# working.net
KiCad netlist of a schematic drawn in EAGLE
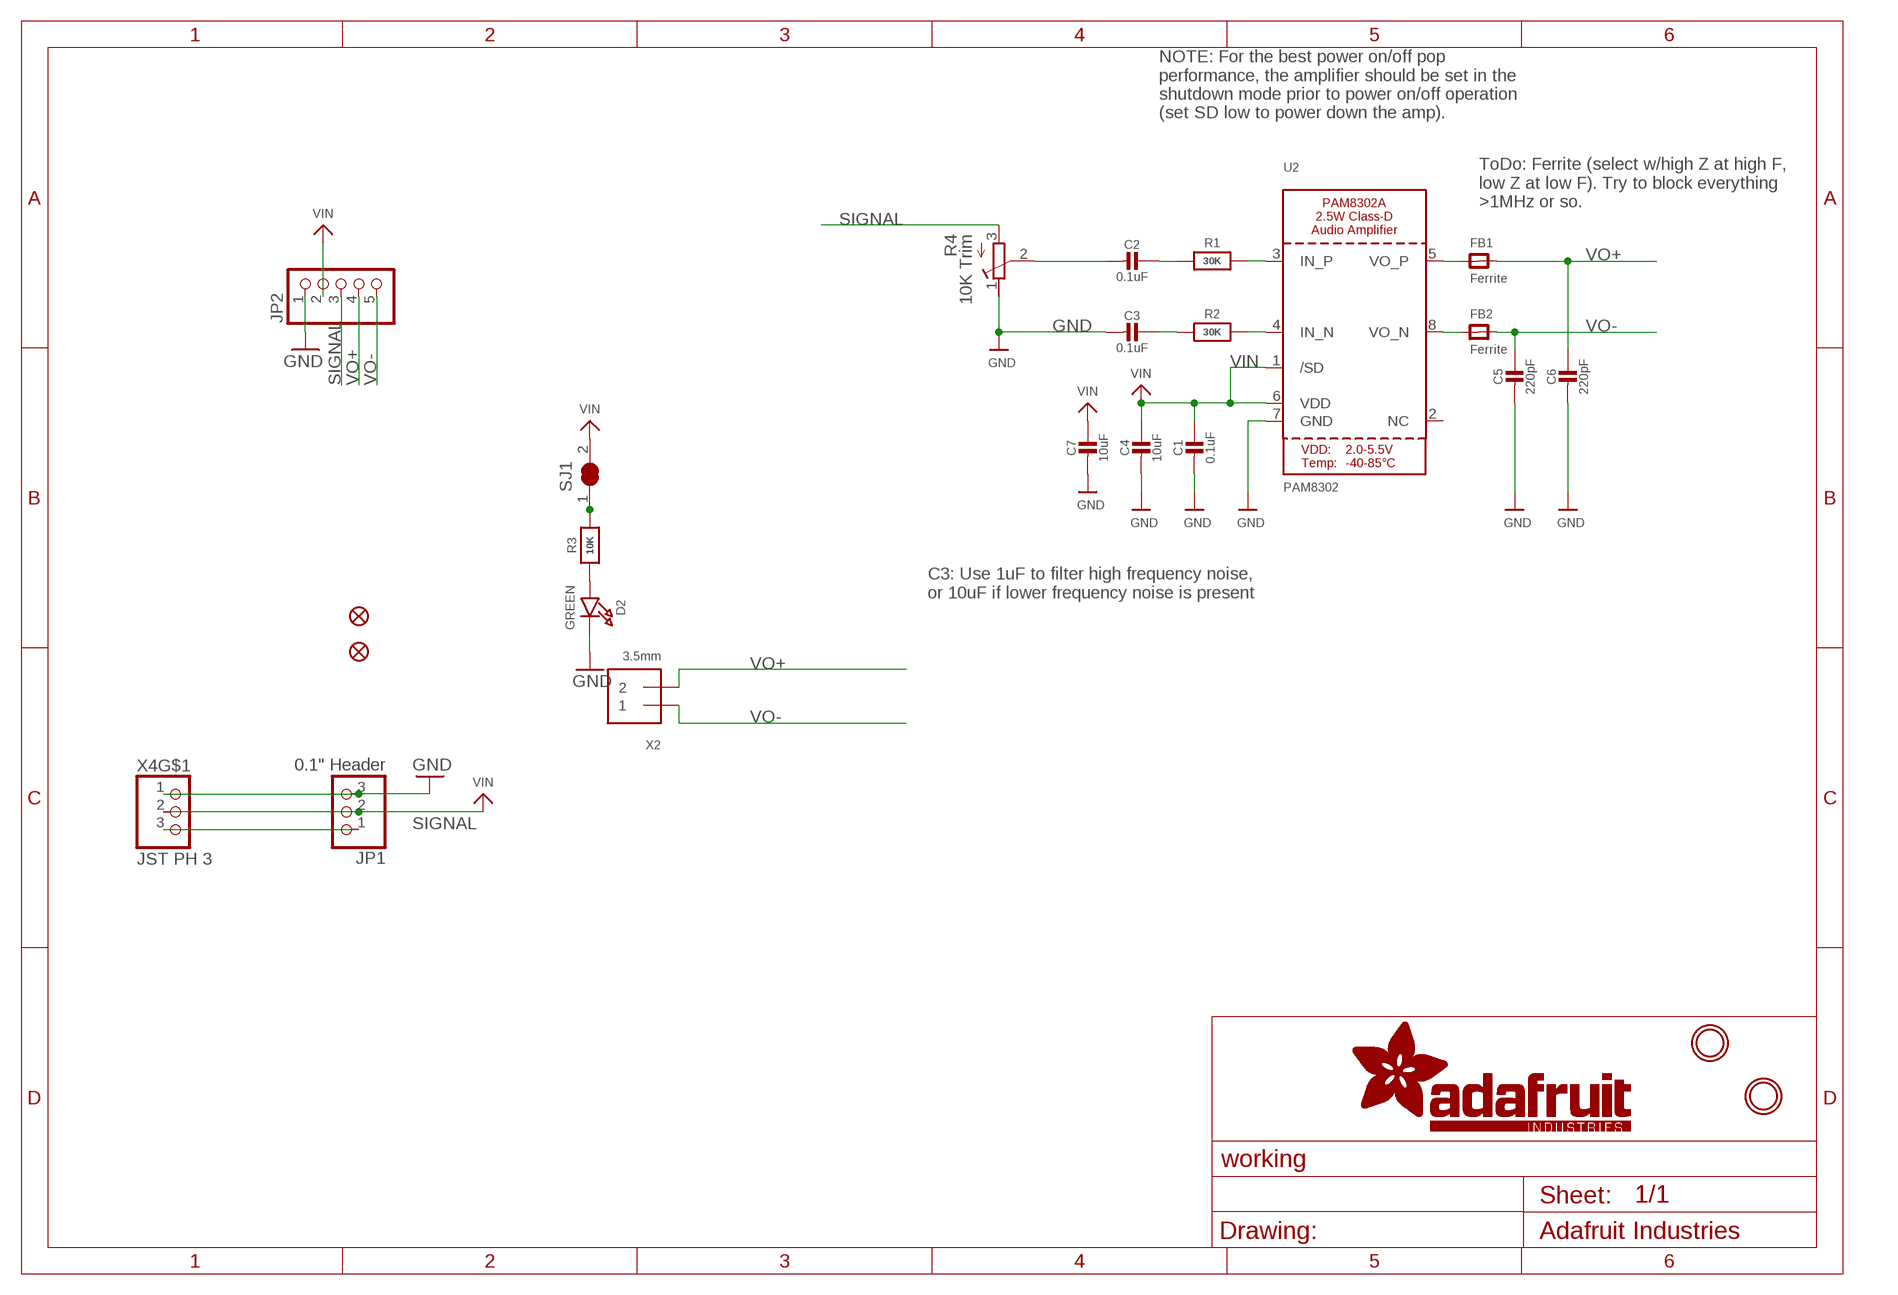
[diagram p0: schematic, sheet 1]

(export (version "E")
  (design (tool "Eeschema 10.0.6"))
  (components
    (comp (ref "C1")
      (value "0.1uF")
      (footprint "eagle-import:0603-NO")
      (libsource (lib "eagle-import") (part "CAP_CERAMIC0603_NO"))
    )
    (comp (ref "C2")
      (value "0.1uF")
      (footprint "eagle-import:0603-NO")
      (libsource (lib "eagle-import") (part "CAP_CERAMIC0603_NO"))
    )
    (comp (ref "C3")
      (value "0.1uF")
      (footprint "eagle-import:0603-NO")
      (libsource (lib "eagle-import") (part "CAP_CERAMIC0603_NO"))
    )
    (comp (ref "C4")
      (value "10uF")
      (footprint "eagle-import:0805-NO")
      (libsource (lib "eagle-import") (part "CAP_CERAMIC0805-NOOUTLINE"))
    )
    (comp (ref "C5")
      (value "220pF")
      (footprint "eagle-import:0603-NO")
      (libsource (lib "eagle-import") (part "CAP_CERAMIC0603_NO"))
    )
    (comp (ref "C6")
      (value "220pF")
      (footprint "eagle-import:0603-NO")
      (libsource (lib "eagle-import") (part "CAP_CERAMIC0603_NO"))
    )
    (comp (ref "C7")
      (value "10uF")
      (footprint "eagle-import:0805-NO")
      (libsource (lib "eagle-import") (part "CAP_CERAMIC0805-NOOUTLINE"))
    )
    (comp (ref "D2")
      (value "GREEN")
      (footprint "eagle-import:CHIPLED_0603_NOOUTLINE")
      (libsource (lib "eagle-import") (part "LED0603_NOOUTLINE"))
    )
    (comp (ref "FB1")
      (value "Ferrite")
      (footprint "eagle-import:0603-NO")
      (libsource (lib "eagle-import") (part "FERRITE-0603NO"))
    )
    (comp (ref "FB2")
      (value "Ferrite")
      (footprint "eagle-import:0603-NO")
      (libsource (lib "eagle-import") (part "FERRITE-0603NO"))
    )
    (comp (ref "FID2")
      (value "FIDUCIAL_1MM")
      (footprint "eagle-import:FIDUCIAL_1MM")
      (libsource (lib "eagle-import") (part "FIDUCIAL_1MM"))
    )
    (comp (ref "FID3")
      (value "FIDUCIAL_1MM")
      (footprint "eagle-import:FIDUCIAL_1MM")
      (libsource (lib "eagle-import") (part "FIDUCIAL_1MM"))
    )
    (comp (ref "JP1")
      (value "0.1\" Header")
      (footprint "eagle-import:1X03_OVAL")
      (libsource (lib "eagle-import") (part "HEADER-1X3"))
    )
    (comp (ref "JP2")
      (value "HEADER-1X570MIL")
      (footprint "eagle-import:1X05_ROUND_70")
      (libsource (lib "eagle-import") (part "HEADER-1X570MIL"))
    )
    (comp (ref "R1")
      (value "30K")
      (footprint "eagle-import:0603-NO")
      (libsource (lib "eagle-import") (part "RESISTOR_0603_NOOUT"))
    )
    (comp (ref "R2")
      (value "30K")
      (footprint "eagle-import:0603-NO")
      (libsource (lib "eagle-import") (part "RESISTOR_0603_NOOUT"))
    )
    (comp (ref "R3")
      (value "10K")
      (footprint "eagle-import:0603-NO")
      (libsource (lib "eagle-import") (part "RESISTOR_0603_NOOUT"))
    )
    (comp (ref "R4")
      (value "10K Trim")
      (footprint "eagle-import:RTRIM3314J")
      (libsource (lib "eagle-import") (part "R-TRIMM3314J"))
    )
    (comp (ref "SJ1")
      (value "SOLDERJUMPER_CLOSED")
      (footprint "eagle-import:SOLDERJUMPER_CLOSEDWIRE")
      (libsource (lib "eagle-import") (part "SOLDERJUMPER_CLOSED"))
    )
    (comp (ref "U$1")
      (value "MOUNTINGHOLE2.5")
      (footprint "eagle-import:MOUNTINGHOLE_2.5_PLATED")
      (libsource (lib "eagle-import") (part "MOUNTINGHOLE2.5"))
    )
    (comp (ref "U$8")
      (value "MOUNTINGHOLE2.5")
      (footprint "eagle-import:MOUNTINGHOLE_2.5_PLATED")
      (libsource (lib "eagle-import") (part "MOUNTINGHOLE2.5"))
    )
    (comp (ref "U2")
      (value "PAM8302")
      (footprint "eagle-import:MSOP8_0.65MM")
      (libsource (lib "eagle-import") (part "AUDIOAMP_PAM8302A"))
    )
    (comp (ref "X2")
      (value "3.5mm")
      (footprint "eagle-import:TERMBLOCK_1X2-3.5MM")
      (libsource (lib "eagle-import") (part "TERMBLOCK_1X2_3.5MM"))
    )
    (comp (ref "X4")
      (value "JST PH 3")
      (footprint "eagle-import:JSTPH3")
      (libsource (lib "eagle-import") (part "CON_JST_PH_3PIN"))
    )
  )
  (nets
    (net (code "1") (name "/SIGNAL") (class "Default")
      (node (ref "JP1") (pin "1") (pinfunction "1_1") (pintype "passive"))
      (node (ref "JP2") (pin "3") (pinfunction "3_3") (pintype "passive"))
      (node (ref "R4") (pin "3") (pinfunction "A_3") (pintype "passive"))
      (node (ref "X4") (pin "3") (pinfunction "3_3") (pintype "passive"))
    )
    (net (code "2") (name "/VO+") (class "Default")
      (node (ref "C6") (pin "1") (pinfunction "1_1") (pintype "passive"))
      (node (ref "FB1") (pin "2") (pinfunction "P$2_2") (pintype "passive"))
      (node (ref "JP2") (pin "4") (pinfunction "4_4") (pintype "passive"))
      (node (ref "X2") (pin "2") (pinfunction "2_2") (pintype "passive"))
    )
    (net (code "3") (name "/VO-") (class "Default")
      (node (ref "C5") (pin "1") (pinfunction "1_1") (pintype "passive"))
      (node (ref "FB2") (pin "2") (pinfunction "P$2_2") (pintype "passive"))
      (node (ref "JP2") (pin "5") (pinfunction "5_5") (pintype "passive"))
      (node (ref "X2") (pin "1") (pinfunction "1_1") (pintype "passive"))
    )
    (net (code "4") (name "GND") (class "Default")
      (node (ref "C1") (pin "2") (pinfunction "2_2") (pintype "passive"))
      (node (ref "C3") (pin "2") (pinfunction "2_2") (pintype "passive"))
      (node (ref "C4") (pin "2") (pinfunction "2_2") (pintype "passive"))
      (node (ref "C5") (pin "2") (pinfunction "2_2") (pintype "passive"))
      (node (ref "C6") (pin "2") (pinfunction "2_2") (pintype "passive"))
      (node (ref "C7") (pin "2") (pinfunction "2_2") (pintype "passive"))
      (node (ref "D2") (pin "C") (pinfunction "C_C") (pintype "passive"))
      (node (ref "JP1") (pin "3") (pinfunction "3_3") (pintype "passive"))
      (node (ref "JP2") (pin "1") (pinfunction "1_1") (pintype "passive"))
      (node (ref "R4") (pin "1") (pinfunction "E_1") (pintype "passive"))
      (node (ref "U2") (pin "7") (pinfunction "GND_7") (pintype "power_in"))
      (node (ref "X4") (pin "1") (pinfunction "1_1") (pintype "passive"))
    )
    (net (code "5") (name "Net-(C2-Pad1)") (class "Default")
      (node (ref "C2") (pin "1") (pinfunction "1_1") (pintype "passive"))
      (node (ref "R1") (pin "1") (pinfunction "1_1") (pintype "passive"))
    )
    (net (code "6") (name "Net-(C3-Pad1)") (class "Default")
      (node (ref "C3") (pin "1") (pinfunction "1_1") (pintype "passive"))
      (node (ref "R2") (pin "1") (pinfunction "1_1") (pintype "passive"))
    )
    (net (code "7") (name "Net-(D2-PadA)") (class "Default")
      (node (ref "D2") (pin "A") (pinfunction "A_A") (pintype "passive"))
      (node (ref "R3") (pin "1") (pinfunction "1_1") (pintype "passive"))
    )
    (net (code "8") (name "Net-(FB1-P$1)") (class "Default")
      (node (ref "FB1") (pin "1") (pinfunction "P$1_1") (pintype "passive"))
      (node (ref "U2") (pin "5") (pinfunction "VO_P_5") (pintype "output"))
    )
    (net (code "9") (name "Net-(FB2-P$1)") (class "Default")
      (node (ref "FB2") (pin "1") (pinfunction "P$1_1") (pintype "passive"))
      (node (ref "U2") (pin "8") (pinfunction "VO_N_8") (pintype "output"))
    )
    (net (code "10") (name "Net-(R3-Pad2)") (class "Default")
      (node (ref "R3") (pin "2") (pinfunction "2_2") (pintype "passive"))
      (node (ref "SJ1") (pin "1") (pinfunction "1_1") (pintype "passive"))
    )
    (net (code "11") (name "Net-(R4-S)") (class "Default")
      (node (ref "C2") (pin "2") (pinfunction "2_2") (pintype "passive"))
      (node (ref "R4") (pin "2") (pinfunction "S_2") (pintype "passive"))
    )
    (net (code "12") (name "Net-(U2-IN_N)") (class "Default")
      (node (ref "R2") (pin "2") (pinfunction "2_2") (pintype "passive"))
      (node (ref "U2") (pin "4") (pinfunction "IN_N_4") (pintype "input"))
    )
    (net (code "13") (name "Net-(U2-IN_P)") (class "Default")
      (node (ref "R1") (pin "2") (pinfunction "2_2") (pintype "passive"))
      (node (ref "U2") (pin "3") (pinfunction "IN_P_3") (pintype "input"))
    )
    (net (code "14") (name "VIN") (class "Default")
      (node (ref "C1") (pin "1") (pinfunction "1_1") (pintype "passive"))
      (node (ref "C4") (pin "1") (pinfunction "1_1") (pintype "passive"))
      (node (ref "C7") (pin "1") (pinfunction "1_1") (pintype "passive"))
      (node (ref "JP1") (pin "2") (pinfunction "2_2") (pintype "passive"))
      (node (ref "JP2") (pin "2") (pinfunction "2_2") (pintype "passive"))
      (node (ref "SJ1") (pin "2") (pinfunction "2_2") (pintype "passive"))
      (node (ref "U2") (pin "1") (pinfunction "/SD_1") (pintype "input"))
      (node (ref "U2") (pin "6") (pinfunction "VDD_6") (pintype "power_in"))
      (node (ref "X4") (pin "2") (pinfunction "2_2") (pintype "passive"))
    )
    (net (code "15") (name "unconnected-(U2-NC-Pad2)") (class "Default")
      (node (ref "U2") (pin "2") (pinfunction "NC_2") (pintype "no_connect"))
    )
  )
)
